# Main.net
KiCad netlist of a schematic drawn in Altium Designer
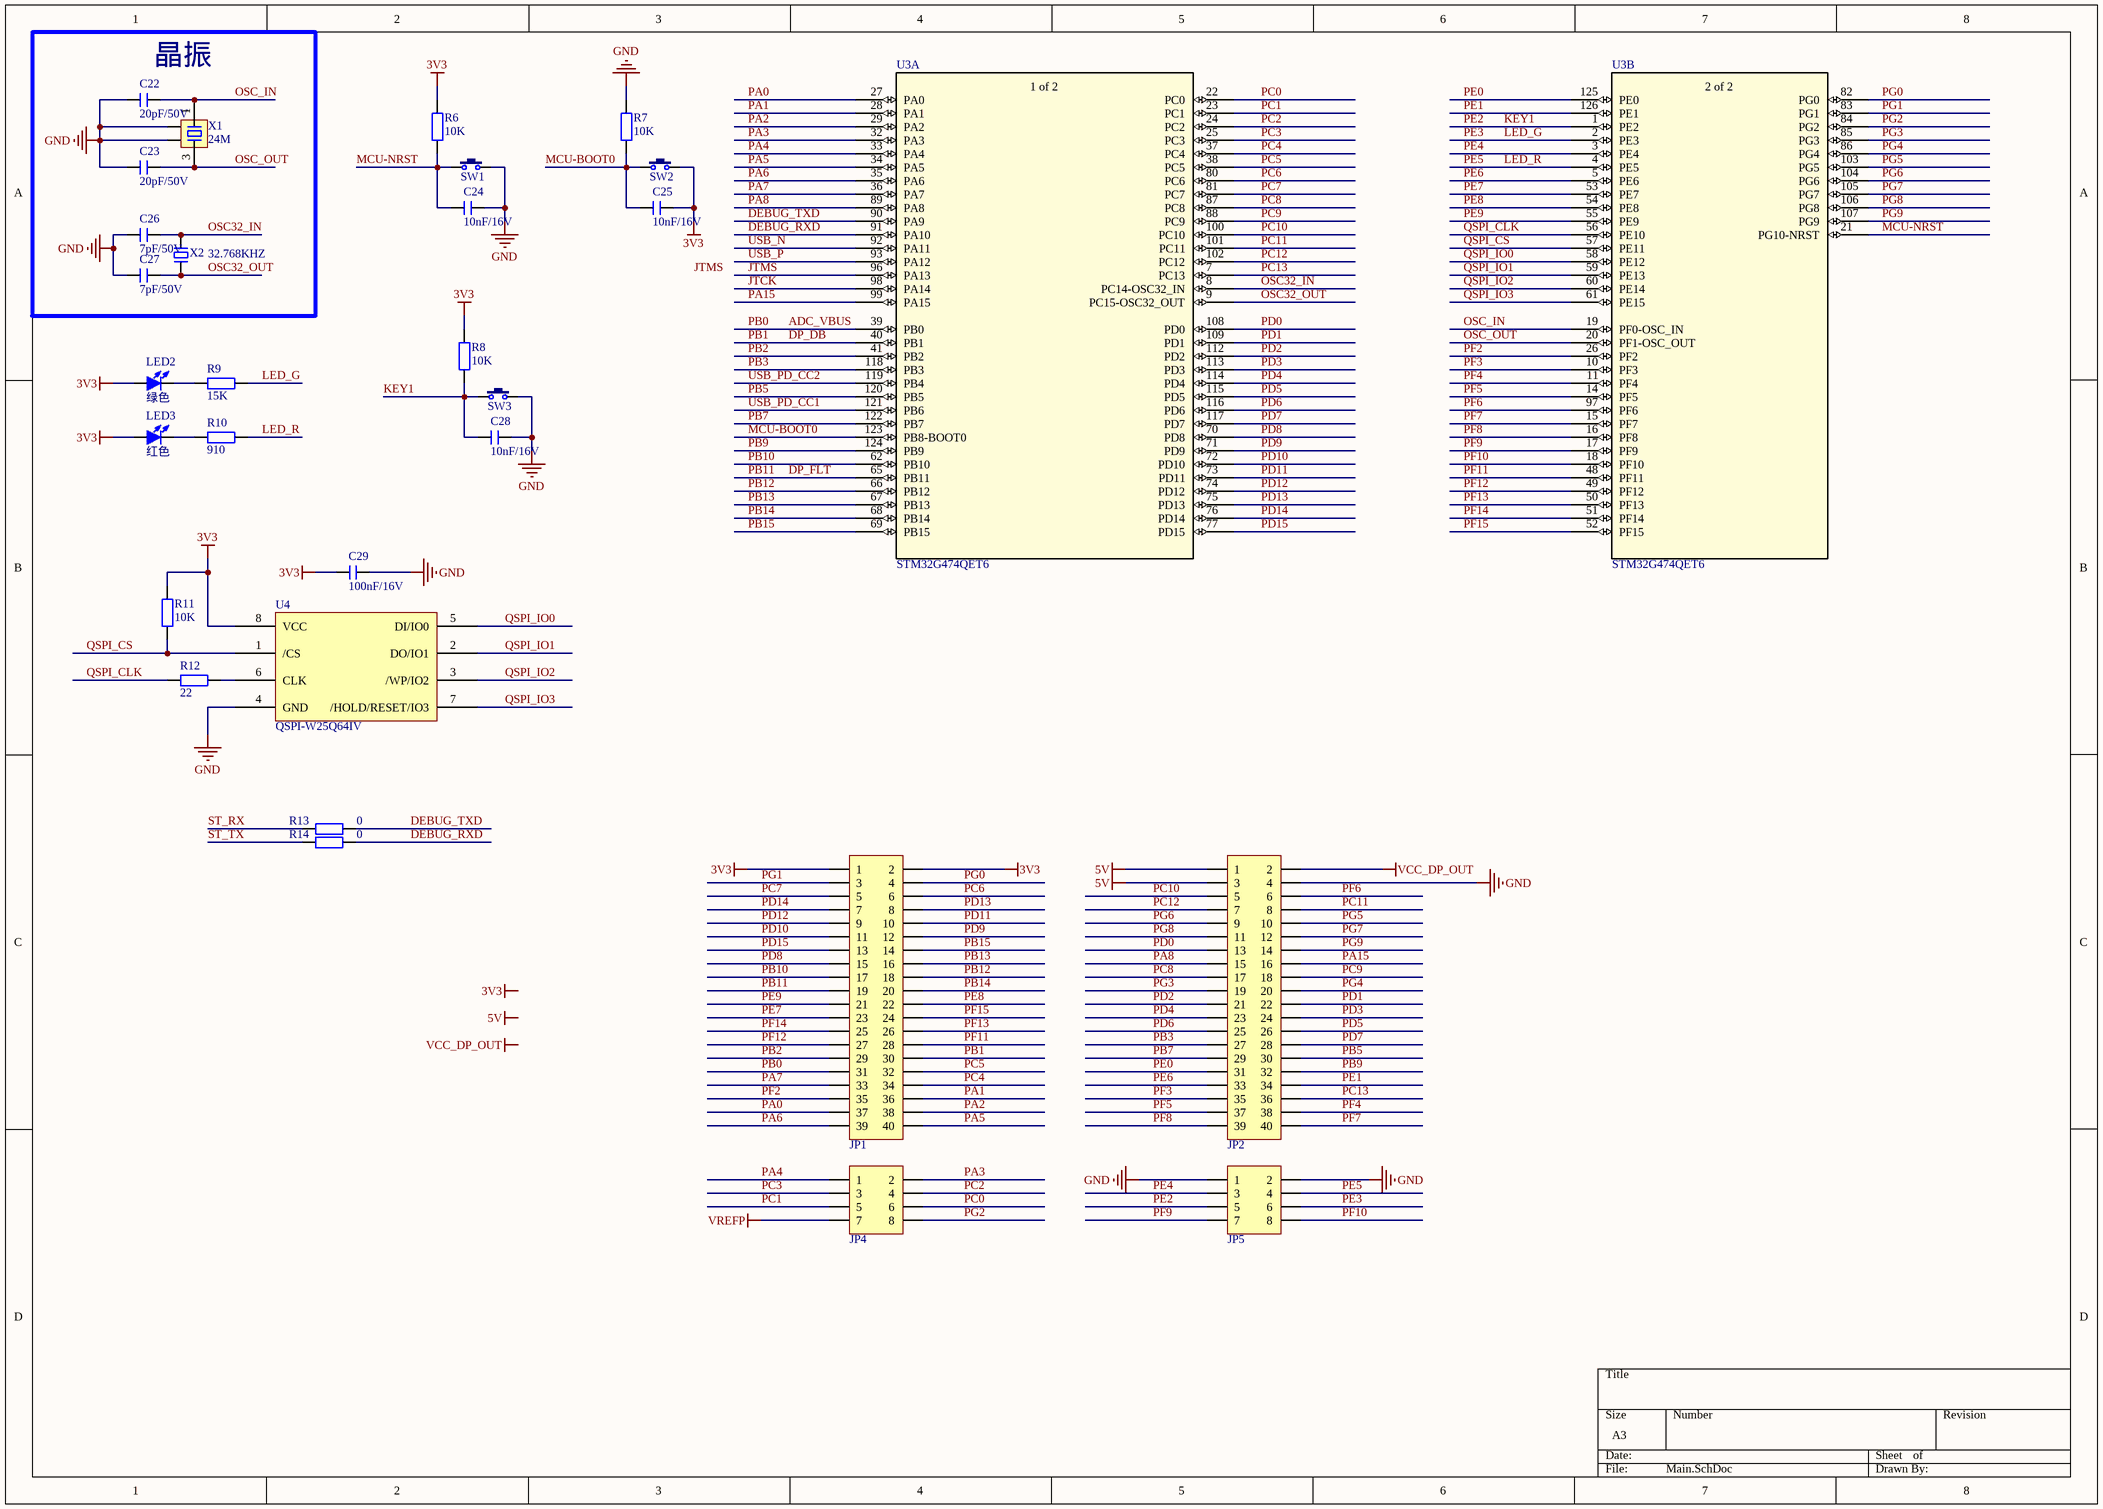
[diagram p0: Main.SchDoc]

(export (version "E")
  (design (tool "Eeschema 10.0.6"))
  (components
    (comp (ref "C22")
      (value "20pF/50V")
      (footprint "C 0402_L")
      (description "贴片电容")
      (libsource (lib "3.1   - 电阻-电容-电感") (part "C"))
    )
    (comp (ref "C23")
      (value "20pF/50V")
      (footprint "C 0402_L")
      (description "贴片电容")
      (libsource (lib "3.1   - 电阻-电容-电感") (part "C"))
    )
    (comp (ref "C24")
      (value "10nF/16V")
      (footprint "C 0402_L")
      (description "贴片电容")
      (libsource (lib "3.1   - 电阻-电容-电感") (part "C"))
    )
    (comp (ref "C25")
      (value "10nF/16V")
      (footprint "C 0402_L")
      (description "贴片电容")
      (libsource (lib "3.1   - 电阻-电容-电感") (part "C"))
    )
    (comp (ref "C26")
      (value "7pF/50V")
      (footprint "C 0402_L")
      (description "贴片电容")
      (libsource (lib "3.1   - 电阻-电容-电感") (part "C"))
    )
    (comp (ref "C27")
      (value "7pF/50V")
      (footprint "C 0402_L")
      (description "贴片电容")
      (libsource (lib "3.1   - 电阻-电容-电感") (part "C"))
    )
    (comp (ref "C28")
      (value "10nF/16V")
      (footprint "C 0402_L")
      (description "贴片电容")
      (libsource (lib "3.1   - 电阻-电容-电感") (part "C"))
    )
    (comp (ref "C29")
      (value "100nF/16V")
      (footprint "C 0402_L")
      (description "贴片电容")
      (libsource (lib "3.1   - 电阻-电容-电感") (part "C"))
    )
    (comp (ref "JP1")
      (value "Header 2X11")
      (footprint "HDR2.54-LI-2x20P")
      (description "20*2P接插件")
      (fields (field (name "版权归属") "源创客"))
      (libsource (lib "4.5   - 接插件-脚距2.54") (part "Header 20X2"))
    )
    (comp (ref "JP2")
      (value "Header 2X11")
      (footprint "HDR2.54-LI-2x20P")
      (description "20*2P接插件")
      (fields (field (name "版权归属") "源创客"))
      (libsource (lib "4.5   - 接插件-脚距2.54") (part "Header 20X2"))
    )
    (comp (ref "JP4")
      (value "Header 4X2")
      (footprint "HDR2.54-LI-2x4P")
      (description "4*2P接插件")
      (fields (field (name "版权归属") "源创客"))
      (libsource (lib "4.5   - 接插件-脚距2.54") (part "Header 4X2"))
    )
    (comp (ref "JP5")
      (value "Header 4X2")
      (footprint "HDR2.54-LI-2x4P")
      (description "4*2P接插件")
      (fields (field (name "版权归属") "源创客"))
      (libsource (lib "4.5   - 接插件-脚距2.54") (part "Header 4X2"))
    )
    (comp (ref "LED2")
      (value "绿色")
      (footprint "LED")
      (description "C84267")
      (libsource (lib "9.1   - LED") (part "LED-SMD"))
    )
    (comp (ref "LED3")
      (value "红色")
      (footprint "LED")
      (description "C84267")
      (libsource (lib "9.1   - LED") (part "LED-SMD"))
    )
    (comp (ref "R6")
      (value "10K")
      (footprint "R 0402_L")
      (description "贴片电阻")
      (libsource (lib "3.1   - 电阻-电容-电感") (part "R"))
    )
    (comp (ref "R7")
      (value "10K")
      (footprint "R 0402_L")
      (description "贴片电阻")
      (libsource (lib "3.1   - 电阻-电容-电感") (part "R"))
    )
    (comp (ref "R8")
      (value "10K")
      (footprint "R 0402_L")
      (description "贴片电阻")
      (libsource (lib "3.1   - 电阻-电容-电感") (part "R"))
    )
    (comp (ref "R9")
      (value "15K")
      (footprint "R 0402_L")
      (description "贴片电阻 0402 5%")
      (libsource (lib "3.1   - 电阻-电容-电感") (part "R"))
    )
    (comp (ref "R10")
      (value "910")
      (footprint "R 0402_L")
      (description "贴片电阻 0402 5%")
      (libsource (lib "3.1   - 电阻-电容-电感") (part "R"))
    )
    (comp (ref "R11")
      (value "10K")
      (footprint "R 0402_L")
      (description "贴片电阻 0402 1%")
      (libsource (lib "3.1   - 电阻-电容-电感") (part "R"))
    )
    (comp (ref "R12")
      (value "22")
      (footprint "R 0402_L")
      (description "贴片电阻 0402 1%")
      (libsource (lib "3.1   - 电阻-电容-电感") (part "R"))
    )
    (comp (ref "R13")
      (value "0")
      (footprint "R 0402_L")
      (description "贴片电阻")
      (libsource (lib "3.1   - 电阻-电容-电感") (part "R"))
    )
    (comp (ref "R14")
      (value "0")
      (footprint "R 0402_L")
      (description "贴片电阻")
      (libsource (lib "3.1   - 电阻-电容-电感") (part "R"))
    )
    (comp (ref "SW1")
      (value "3x6x5")
      (footprint "按钮")
      (description "3x6轻触开关")
      (libsource (lib "5.1   - 按键-开关") (part "TSW 3x6"))
    )
    (comp (ref "SW2")
      (value "3x6x5")
      (footprint "按钮")
      (description "3x6轻触开关")
      (libsource (lib "5.1   - 按键-开关") (part "TSW 3x6"))
    )
    (comp (ref "SW3")
      (value "3x6x5")
      (footprint "按钮")
      (description "3x6轻触开关")
      (libsource (lib "5.1   - 按键-开关") (part "TSW 3x6"))
    )
    (comp (ref "U3")
      (value "STM32G474QET6")
      (footprint "LQFP128 14x14_L")
      (description "No Description Available")
      (fields (field (name "COPYRIGHT") "Copyright (C) 2018 Accelerated Designs. All rights reserved"))
      (libsource (lib "2021-04-22_13-53-57") (part "STM32G474QET6"))
    )
    (comp (ref "U4")
      (value "QSPI-W25Q64IV")
      (footprint "QSPI")
      (libsource (lib "AltiumV15") (part "QSPI-W25Q256IV"))
    )
    (comp (ref "X1")
      (value "24M")
      (footprint "OSC 3225-4P")
      (description "4脚无源晶振")
      (libsource (lib "10.1 - 保险丝-晶振") (part "XTAL-4P"))
    )
    (comp (ref "X2")
      (value "32.768KHZ")
      (footprint "OSC 3215-2P")
      (description "2脚无源脚晶振")
      (libsource (lib "10.1 - 保险丝-晶振") (part "XTAL-2P"))
    )
  )
  (nets
    (net (code "1") (name "/ADC_VBUS") (class "Default")
      (node (ref "JP1") (pin "31") (pinfunction "31_31") (pintype "passive"))
      (node (ref "U3") (pin "39") (pinfunction "PB0_39") (pintype "bidirectional"))
    )
    (net (code "2") (name "/DEBUG_RXD") (class "Default")
      (node (ref "R14") (pin "2") (pinfunction "2_2") (pintype "passive"))
      (node (ref "U3") (pin "91") (pinfunction "PA10_91") (pintype "bidirectional"))
    )
    (net (code "3") (name "/DEBUG_TXD") (class "Default")
      (node (ref "R13") (pin "2") (pinfunction "2_2") (pintype "passive"))
      (node (ref "U3") (pin "90") (pinfunction "PA9_90") (pintype "bidirectional"))
    )
    (net (code "4") (name "/DP_DB") (class "Default")
      (node (ref "JP1") (pin "30") (pinfunction "30_30") (pintype "passive"))
      (node (ref "U3") (pin "40") (pinfunction "PB1_40") (pintype "bidirectional"))
    )
    (net (code "5") (name "/DP_FLT") (class "Default")
      (node (ref "JP1") (pin "19") (pinfunction "19_19") (pintype "passive"))
      (node (ref "U3") (pin "65") (pinfunction "PB11_65") (pintype "bidirectional"))
    )
    (net (code "6") (name "/JTCK") (class "Default")
      (node (ref "U3") (pin "98") (pinfunction "PA14_98") (pintype "bidirectional"))
    )
    (net (code "7") (name "/JTMS") (class "Default")
      (node (ref "U3") (pin "96") (pinfunction "PA13_96") (pintype "bidirectional"))
    )
    (net (code "8") (name "/KEY1") (class "Default")
      (node (ref "C28") (pin "1") (pinfunction "1_1") (pintype "passive"))
      (node (ref "JP5") (pin "5") (pinfunction "5_5") (pintype "passive"))
      (node (ref "R8") (pin "1") (pinfunction "1_1") (pintype "passive"))
      (node (ref "SW3") (pin "1") (pinfunction "1_1") (pintype "passive"))
      (node (ref "U3") (pin "1") (pinfunction "PE2_1") (pintype "bidirectional"))
    )
    (net (code "9") (name "/LED_G") (class "Default")
      (node (ref "JP5") (pin "6") (pinfunction "6_6") (pintype "passive"))
      (node (ref "R9") (pin "1") (pinfunction "1_1") (pintype "passive"))
      (node (ref "U3") (pin "2") (pinfunction "PE3_2") (pintype "bidirectional"))
    )
    (net (code "10") (name "/LED_R") (class "Default")
      (node (ref "JP5") (pin "4") (pinfunction "4_4") (pintype "passive"))
      (node (ref "R10") (pin "1") (pinfunction "1_1") (pintype "passive"))
      (node (ref "U3") (pin "4") (pinfunction "PE5_4") (pintype "bidirectional"))
    )
    (net (code "11") (name "/MCU-BOOT0") (class "Default")
      (node (ref "C25") (pin "1") (pinfunction "1_1") (pintype "passive"))
      (node (ref "R7") (pin "1") (pinfunction "1_1") (pintype "passive"))
      (node (ref "SW2") (pin "1") (pinfunction "1_1") (pintype "passive"))
      (node (ref "U3") (pin "123") (pinfunction "PB8-BOOT0_123") (pintype "bidirectional"))
    )
    (net (code "12") (name "/MCU-NRST") (class "Default")
      (node (ref "C24") (pin "1") (pinfunction "1_1") (pintype "passive"))
      (node (ref "R6") (pin "1") (pinfunction "1_1") (pintype "passive"))
      (node (ref "SW1") (pin "1") (pinfunction "1_1") (pintype "passive"))
      (node (ref "U3") (pin "21") (pinfunction "PG10-NRST_21") (pintype "bidirectional"))
    )
    (net (code "13") (name "/OSC32_IN") (class "Default")
      (node (ref "C26") (pin "2") (pinfunction "2_2") (pintype "passive"))
      (node (ref "U3") (pin "8") (pinfunction "PC14-OSC32_IN_8") (pintype "bidirectional"))
      (node (ref "X2") (pin "2") (pinfunction "2_2") (pintype "passive"))
    )
    (net (code "14") (name "/OSC32_OUT") (class "Default")
      (node (ref "C27") (pin "2") (pinfunction "2_2") (pintype "passive"))
      (node (ref "U3") (pin "9") (pinfunction "PC15-OSC32_OUT_9") (pintype "bidirectional"))
      (node (ref "X2") (pin "1") (pinfunction "1_1") (pintype "passive"))
    )
    (net (code "15") (name "/OSC_IN") (class "Default")
      (node (ref "C22") (pin "2") (pinfunction "2_2") (pintype "passive"))
      (node (ref "U3") (pin "19") (pinfunction "PF0-OSC_IN_19") (pintype "bidirectional"))
      (node (ref "X1") (pin "1") (pinfunction "1_1") (pintype "passive"))
    )
    (net (code "16") (name "/OSC_OUT") (class "Default")
      (node (ref "C23") (pin "2") (pinfunction "2_2") (pintype "passive"))
      (node (ref "U3") (pin "20") (pinfunction "PF1-OSC_OUT_20") (pintype "bidirectional"))
      (node (ref "X1") (pin "3") (pinfunction "3_3") (pintype "passive"))
    )
    (net (code "17") (name "/PA0") (class "Default")
      (node (ref "JP1") (pin "37") (pinfunction "37_37") (pintype "passive"))
      (node (ref "U3") (pin "27") (pinfunction "PA0_27") (pintype "bidirectional"))
    )
    (net (code "18") (name "/PA1") (class "Default")
      (node (ref "JP1") (pin "36") (pinfunction "36_36") (pintype "passive"))
      (node (ref "U3") (pin "28") (pinfunction "PA1_28") (pintype "bidirectional"))
    )
    (net (code "19") (name "/PA2") (class "Default")
      (node (ref "JP1") (pin "38") (pinfunction "38_38") (pintype "passive"))
      (node (ref "U3") (pin "29") (pinfunction "PA2_29") (pintype "bidirectional"))
    )
    (net (code "20") (name "/PA3") (class "Default")
      (node (ref "JP4") (pin "2") (pinfunction "2_2") (pintype "passive"))
      (node (ref "U3") (pin "32") (pinfunction "PA3_32") (pintype "bidirectional"))
    )
    (net (code "21") (name "/PA4") (class "Default")
      (node (ref "JP4") (pin "1") (pinfunction "1_1") (pintype "passive"))
      (node (ref "U3") (pin "33") (pinfunction "PA4_33") (pintype "bidirectional"))
    )
    (net (code "22") (name "/PA5") (class "Default")
      (node (ref "JP1") (pin "40") (pinfunction "40_40") (pintype "passive"))
      (node (ref "U3") (pin "34") (pinfunction "PA5_34") (pintype "bidirectional"))
    )
    (net (code "23") (name "/PA6") (class "Default")
      (node (ref "JP1") (pin "39") (pinfunction "39_39") (pintype "passive"))
      (node (ref "U3") (pin "35") (pinfunction "PA6_35") (pintype "bidirectional"))
    )
    (net (code "24") (name "/PA7") (class "Default")
      (node (ref "JP1") (pin "33") (pinfunction "33_33") (pintype "passive"))
      (node (ref "U3") (pin "36") (pinfunction "PA7_36") (pintype "bidirectional"))
    )
    (net (code "25") (name "/PA8") (class "Default")
      (node (ref "JP2") (pin "15") (pinfunction "15_15") (pintype "passive"))
      (node (ref "U3") (pin "89") (pinfunction "PA8_89") (pintype "bidirectional"))
    )
    (net (code "26") (name "/PA15") (class "Default")
      (node (ref "JP2") (pin "16") (pinfunction "16_16") (pintype "passive"))
      (node (ref "U3") (pin "99") (pinfunction "PA15_99") (pintype "bidirectional"))
    )
    (net (code "27") (name "/PB2") (class "Default")
      (node (ref "JP1") (pin "29") (pinfunction "29_29") (pintype "passive"))
      (node (ref "U3") (pin "41") (pinfunction "PB2_41") (pintype "bidirectional"))
    )
    (net (code "28") (name "/PB3") (class "Default")
      (node (ref "JP2") (pin "27") (pinfunction "27_27") (pintype "passive"))
      (node (ref "U3") (pin "118") (pinfunction "PB3_118") (pintype "bidirectional"))
    )
    (net (code "29") (name "/PB5") (class "Default")
      (node (ref "JP2") (pin "30") (pinfunction "30_30") (pintype "passive"))
      (node (ref "U3") (pin "120") (pinfunction "PB5_120") (pintype "bidirectional"))
    )
    (net (code "30") (name "/PB7") (class "Default")
      (node (ref "JP2") (pin "29") (pinfunction "29_29") (pintype "passive"))
      (node (ref "U3") (pin "122") (pinfunction "PB7_122") (pintype "bidirectional"))
    )
    (net (code "31") (name "/PB9") (class "Default")
      (node (ref "JP2") (pin "32") (pinfunction "32_32") (pintype "passive"))
      (node (ref "U3") (pin "124") (pinfunction "PB9_124") (pintype "bidirectional"))
    )
    (net (code "32") (name "/PB10") (class "Default")
      (node (ref "JP1") (pin "17") (pinfunction "17_17") (pintype "passive"))
      (node (ref "U3") (pin "62") (pinfunction "PB10_62") (pintype "bidirectional"))
    )
    (net (code "33") (name "/PB12") (class "Default")
      (node (ref "JP1") (pin "18") (pinfunction "18_18") (pintype "passive"))
      (node (ref "U3") (pin "66") (pinfunction "PB12_66") (pintype "bidirectional"))
    )
    (net (code "34") (name "/PB13") (class "Default")
      (node (ref "JP1") (pin "16") (pinfunction "16_16") (pintype "passive"))
      (node (ref "U3") (pin "67") (pinfunction "PB13_67") (pintype "bidirectional"))
    )
    (net (code "35") (name "/PB14") (class "Default")
      (node (ref "JP1") (pin "20") (pinfunction "20_20") (pintype "passive"))
      (node (ref "U3") (pin "68") (pinfunction "PB14_68") (pintype "bidirectional"))
    )
    (net (code "36") (name "/PB15") (class "Default")
      (node (ref "JP1") (pin "14") (pinfunction "14_14") (pintype "passive"))
      (node (ref "U3") (pin "69") (pinfunction "PB15_69") (pintype "bidirectional"))
    )
    (net (code "37") (name "/PC0") (class "Default")
      (node (ref "JP4") (pin "6") (pinfunction "6_6") (pintype "passive"))
      (node (ref "U3") (pin "22") (pinfunction "PC0_22") (pintype "bidirectional"))
    )
    (net (code "38") (name "/PC1") (class "Default")
      (node (ref "JP4") (pin "5") (pinfunction "5_5") (pintype "passive"))
      (node (ref "U3") (pin "23") (pinfunction "PC1_23") (pintype "bidirectional"))
    )
    (net (code "39") (name "/PC2") (class "Default")
      (node (ref "JP4") (pin "4") (pinfunction "4_4") (pintype "passive"))
      (node (ref "U3") (pin "24") (pinfunction "PC2_24") (pintype "bidirectional"))
    )
    (net (code "40") (name "/PC3") (class "Default")
      (node (ref "JP4") (pin "3") (pinfunction "3_3") (pintype "passive"))
      (node (ref "U3") (pin "25") (pinfunction "PC3_25") (pintype "bidirectional"))
    )
    (net (code "41") (name "/PC4") (class "Default")
      (node (ref "JP1") (pin "34") (pinfunction "34_34") (pintype "passive"))
      (node (ref "U3") (pin "37") (pinfunction "PC4_37") (pintype "bidirectional"))
    )
    (net (code "42") (name "/PC5") (class "Default")
      (node (ref "JP1") (pin "32") (pinfunction "32_32") (pintype "passive"))
      (node (ref "U3") (pin "38") (pinfunction "PC5_38") (pintype "bidirectional"))
    )
    (net (code "43") (name "/PC6") (class "Default")
      (node (ref "JP1") (pin "6") (pinfunction "6_6") (pintype "passive"))
      (node (ref "U3") (pin "80") (pinfunction "PC6_80") (pintype "bidirectional"))
    )
    (net (code "44") (name "/PC7") (class "Default")
      (node (ref "JP1") (pin "5") (pinfunction "5_5") (pintype "passive"))
      (node (ref "U3") (pin "81") (pinfunction "PC7_81") (pintype "bidirectional"))
    )
    (net (code "45") (name "/PC8") (class "Default")
      (node (ref "JP2") (pin "17") (pinfunction "17_17") (pintype "passive"))
      (node (ref "U3") (pin "87") (pinfunction "PC8_87") (pintype "bidirectional"))
    )
    (net (code "46") (name "/PC9") (class "Default")
      (node (ref "JP2") (pin "18") (pinfunction "18_18") (pintype "passive"))
      (node (ref "U3") (pin "88") (pinfunction "PC9_88") (pintype "bidirectional"))
    )
    (net (code "47") (name "/PC10") (class "Default")
      (node (ref "JP2") (pin "5") (pinfunction "5_5") (pintype "passive"))
      (node (ref "U3") (pin "100") (pinfunction "PC10_100") (pintype "bidirectional"))
    )
    (net (code "48") (name "/PC11") (class "Default")
      (node (ref "JP2") (pin "8") (pinfunction "8_8") (pintype "passive"))
      (node (ref "U3") (pin "101") (pinfunction "PC11_101") (pintype "bidirectional"))
    )
    (net (code "49") (name "/PC12") (class "Default")
      (node (ref "JP2") (pin "7") (pinfunction "7_7") (pintype "passive"))
      (node (ref "U3") (pin "102") (pinfunction "PC12_102") (pintype "bidirectional"))
    )
    (net (code "50") (name "/PC13") (class "Default")
      (node (ref "JP2") (pin "36") (pinfunction "36_36") (pintype "passive"))
      (node (ref "U3") (pin "7") (pinfunction "PC13_7") (pintype "bidirectional"))
    )
    (net (code "51") (name "/PD0") (class "Default")
      (node (ref "JP2") (pin "13") (pinfunction "13_13") (pintype "passive"))
      (node (ref "U3") (pin "108") (pinfunction "PD0_108") (pintype "bidirectional"))
    )
    (net (code "52") (name "/PD1") (class "Default")
      (node (ref "JP2") (pin "22") (pinfunction "22_22") (pintype "passive"))
      (node (ref "U3") (pin "109") (pinfunction "PD1_109") (pintype "bidirectional"))
    )
    (net (code "53") (name "/PD2") (class "Default")
      (node (ref "JP2") (pin "21") (pinfunction "21_21") (pintype "passive"))
      (node (ref "U3") (pin "112") (pinfunction "PD2_112") (pintype "bidirectional"))
    )
    (net (code "54") (name "/PD3") (class "Default")
      (node (ref "JP2") (pin "24") (pinfunction "24_24") (pintype "passive"))
      (node (ref "U3") (pin "113") (pinfunction "PD3_113") (pintype "bidirectional"))
    )
    (net (code "55") (name "/PD4") (class "Default")
      (node (ref "JP2") (pin "23") (pinfunction "23_23") (pintype "passive"))
      (node (ref "U3") (pin "114") (pinfunction "PD4_114") (pintype "bidirectional"))
    )
    (net (code "56") (name "/PD5") (class "Default")
      (node (ref "JP2") (pin "26") (pinfunction "26_26") (pintype "passive"))
      (node (ref "U3") (pin "115") (pinfunction "PD5_115") (pintype "bidirectional"))
    )
    (net (code "57") (name "/PD6") (class "Default")
      (node (ref "JP2") (pin "25") (pinfunction "25_25") (pintype "passive"))
      (node (ref "U3") (pin "116") (pinfunction "PD6_116") (pintype "bidirectional"))
    )
    (net (code "58") (name "/PD7") (class "Default")
      (node (ref "JP2") (pin "28") (pinfunction "28_28") (pintype "passive"))
      (node (ref "U3") (pin "117") (pinfunction "PD7_117") (pintype "bidirectional"))
    )
    (net (code "59") (name "/PD8") (class "Default")
      (node (ref "JP1") (pin "15") (pinfunction "15_15") (pintype "passive"))
      (node (ref "U3") (pin "70") (pinfunction "PD8_70") (pintype "bidirectional"))
    )
    (net (code "60") (name "/PD9") (class "Default")
      (node (ref "JP1") (pin "12") (pinfunction "12_12") (pintype "passive"))
      (node (ref "U3") (pin "71") (pinfunction "PD9_71") (pintype "bidirectional"))
    )
    (net (code "61") (name "/PD10") (class "Default")
      (node (ref "JP1") (pin "11") (pinfunction "11_11") (pintype "passive"))
      (node (ref "U3") (pin "72") (pinfunction "PD10_72") (pintype "bidirectional"))
    )
    (net (code "62") (name "/PD11") (class "Default")
      (node (ref "JP1") (pin "10") (pinfunction "10_10") (pintype "passive"))
      (node (ref "U3") (pin "73") (pinfunction "PD11_73") (pintype "bidirectional"))
    )
    (net (code "63") (name "/PD12") (class "Default")
      (node (ref "JP1") (pin "9") (pinfunction "9_9") (pintype "passive"))
      (node (ref "U3") (pin "74") (pinfunction "PD12_74") (pintype "bidirectional"))
    )
    (net (code "64") (name "/PD13") (class "Default")
      (node (ref "JP1") (pin "8") (pinfunction "8_8") (pintype "passive"))
      (node (ref "U3") (pin "75") (pinfunction "PD13_75") (pintype "bidirectional"))
    )
    (net (code "65") (name "/PD14") (class "Default")
      (node (ref "JP1") (pin "7") (pinfunction "7_7") (pintype "passive"))
      (node (ref "U3") (pin "76") (pinfunction "PD14_76") (pintype "bidirectional"))
    )
    (net (code "66") (name "/PD15") (class "Default")
      (node (ref "JP1") (pin "13") (pinfunction "13_13") (pintype "passive"))
      (node (ref "U3") (pin "77") (pinfunction "PD15_77") (pintype "bidirectional"))
    )
    (net (code "67") (name "/PE0") (class "Default")
      (node (ref "JP2") (pin "31") (pinfunction "31_31") (pintype "passive"))
      (node (ref "U3") (pin "125") (pinfunction "PE0_125") (pintype "bidirectional"))
    )
    (net (code "68") (name "/PE1") (class "Default")
      (node (ref "JP2") (pin "34") (pinfunction "34_34") (pintype "passive"))
      (node (ref "U3") (pin "126") (pinfunction "PE1_126") (pintype "bidirectional"))
    )
    (net (code "69") (name "/PE4") (class "Default")
      (node (ref "JP5") (pin "3") (pinfunction "3_3") (pintype "passive"))
      (node (ref "U3") (pin "3") (pinfunction "PE4_3") (pintype "bidirectional"))
    )
    (net (code "70") (name "/PE6") (class "Default")
      (node (ref "JP2") (pin "33") (pinfunction "33_33") (pintype "passive"))
      (node (ref "U3") (pin "5") (pinfunction "PE6_5") (pintype "bidirectional"))
    )
    (net (code "71") (name "/PE7") (class "Default")
      (node (ref "JP1") (pin "23") (pinfunction "23_23") (pintype "passive"))
      (node (ref "U3") (pin "53") (pinfunction "PE7_53") (pintype "bidirectional"))
    )
    (net (code "72") (name "/PE8") (class "Default")
      (node (ref "JP1") (pin "22") (pinfunction "22_22") (pintype "passive"))
      (node (ref "U3") (pin "54") (pinfunction "PE8_54") (pintype "bidirectional"))
    )
    (net (code "73") (name "/PE9") (class "Default")
      (node (ref "JP1") (pin "21") (pinfunction "21_21") (pintype "passive"))
      (node (ref "U3") (pin "55") (pinfunction "PE9_55") (pintype "bidirectional"))
    )
    (net (code "74") (name "/PF2") (class "Default")
      (node (ref "JP1") (pin "35") (pinfunction "35_35") (pintype "passive"))
      (node (ref "U3") (pin "26") (pinfunction "PF2_26") (pintype "bidirectional"))
    )
    (net (code "75") (name "/PF3") (class "Default")
      (node (ref "JP2") (pin "35") (pinfunction "35_35") (pintype "passive"))
      (node (ref "U3") (pin "10") (pinfunction "PF3_10") (pintype "bidirectional"))
    )
    (net (code "76") (name "/PF4") (class "Default")
      (node (ref "JP2") (pin "38") (pinfunction "38_38") (pintype "passive"))
      (node (ref "U3") (pin "11") (pinfunction "PF4_11") (pintype "bidirectional"))
    )
    (net (code "77") (name "/PF5") (class "Default")
      (node (ref "JP2") (pin "37") (pinfunction "37_37") (pintype "passive"))
      (node (ref "U3") (pin "14") (pinfunction "PF5_14") (pintype "bidirectional"))
    )
    (net (code "78") (name "/PF6") (class "Default")
      (node (ref "JP2") (pin "6") (pinfunction "6_6") (pintype "passive"))
      (node (ref "U3") (pin "97") (pinfunction "PF6_97") (pintype "bidirectional"))
    )
    (net (code "79") (name "/PF7") (class "Default")
      (node (ref "JP2") (pin "40") (pinfunction "40_40") (pintype "passive"))
      (node (ref "U3") (pin "15") (pinfunction "PF7_15") (pintype "bidirectional"))
    )
    (net (code "80") (name "/PF8") (class "Default")
      (node (ref "JP2") (pin "39") (pinfunction "39_39") (pintype "passive"))
      (node (ref "U3") (pin "16") (pinfunction "PF8_16") (pintype "bidirectional"))
    )
    (net (code "81") (name "/PF9") (class "Default")
      (node (ref "JP5") (pin "7") (pinfunction "7_7") (pintype "passive"))
      (node (ref "U3") (pin "17") (pinfunction "PF9_17") (pintype "bidirectional"))
    )
    (net (code "82") (name "/PF10") (class "Default")
      (node (ref "JP5") (pin "8") (pinfunction "8_8") (pintype "passive"))
      (node (ref "U3") (pin "18") (pinfunction "PF10_18") (pintype "bidirectional"))
    )
    (net (code "83") (name "/PF11") (class "Default")
      (node (ref "JP1") (pin "28") (pinfunction "28_28") (pintype "passive"))
      (node (ref "U3") (pin "48") (pinfunction "PF11_48") (pintype "bidirectional"))
    )
    (net (code "84") (name "/PF12") (class "Default")
      (node (ref "JP1") (pin "27") (pinfunction "27_27") (pintype "passive"))
      (node (ref "U3") (pin "49") (pinfunction "PF12_49") (pintype "bidirectional"))
    )
    (net (code "85") (name "/PF13") (class "Default")
      (node (ref "JP1") (pin "26") (pinfunction "26_26") (pintype "passive"))
      (node (ref "U3") (pin "50") (pinfunction "PF13_50") (pintype "bidirectional"))
    )
    (net (code "86") (name "/PF14") (class "Default")
      (node (ref "JP1") (pin "25") (pinfunction "25_25") (pintype "passive"))
      (node (ref "U3") (pin "51") (pinfunction "PF14_51") (pintype "bidirectional"))
    )
    (net (code "87") (name "/PF15") (class "Default")
      (node (ref "JP1") (pin "24") (pinfunction "24_24") (pintype "passive"))
      (node (ref "U3") (pin "52") (pinfunction "PF15_52") (pintype "bidirectional"))
    )
    (net (code "88") (name "/PG0") (class "Default")
      (node (ref "JP1") (pin "4") (pinfunction "4_4") (pintype "passive"))
      (node (ref "U3") (pin "82") (pinfunction "PG0_82") (pintype "bidirectional"))
    )
    (net (code "89") (name "/PG1") (class "Default")
      (node (ref "JP1") (pin "3") (pinfunction "3_3") (pintype "passive"))
      (node (ref "U3") (pin "83") (pinfunction "PG1_83") (pintype "bidirectional"))
    )
    (net (code "90") (name "/PG2") (class "Default")
      (node (ref "JP4") (pin "8") (pinfunction "8_8") (pintype "passive"))
      (node (ref "U3") (pin "84") (pinfunction "PG2_84") (pintype "bidirectional"))
    )
    (net (code "91") (name "/PG3") (class "Default")
      (node (ref "JP2") (pin "19") (pinfunction "19_19") (pintype "passive"))
      (node (ref "U3") (pin "85") (pinfunction "PG3_85") (pintype "bidirectional"))
    )
    (net (code "92") (name "/PG4") (class "Default")
      (node (ref "JP2") (pin "20") (pinfunction "20_20") (pintype "passive"))
      (node (ref "U3") (pin "86") (pinfunction "PG4_86") (pintype "bidirectional"))
    )
    (net (code "93") (name "/PG5") (class "Default")
      (node (ref "JP2") (pin "10") (pinfunction "10_10") (pintype "passive"))
      (node (ref "U3") (pin "103") (pinfunction "PG5_103") (pintype "bidirectional"))
    )
    (net (code "94") (name "/PG6") (class "Default")
      (node (ref "JP2") (pin "9") (pinfunction "9_9") (pintype "passive"))
      (node (ref "U3") (pin "104") (pinfunction "PG6_104") (pintype "bidirectional"))
    )
    (net (code "95") (name "/PG7") (class "Default")
      (node (ref "JP2") (pin "12") (pinfunction "12_12") (pintype "passive"))
      (node (ref "U3") (pin "105") (pinfunction "PG7_105") (pintype "bidirectional"))
    )
    (net (code "96") (name "/PG8") (class "Default")
      (node (ref "JP2") (pin "11") (pinfunction "11_11") (pintype "passive"))
      (node (ref "U3") (pin "106") (pinfunction "PG8_106") (pintype "bidirectional"))
    )
    (net (code "97") (name "/PG9") (class "Default")
      (node (ref "JP2") (pin "14") (pinfunction "14_14") (pintype "passive"))
      (node (ref "U3") (pin "107") (pinfunction "PG9_107") (pintype "bidirectional"))
    )
    (net (code "98") (name "/QSPI_CLK") (class "Default")
      (node (ref "R12") (pin "1") (pinfunction "1_1") (pintype "passive"))
      (node (ref "U3") (pin "56") (pinfunction "PE10_56") (pintype "bidirectional"))
    )
    (net (code "99") (name "/QSPI_CS") (class "Default")
      (node (ref "R11") (pin "2") (pinfunction "2_2") (pintype "passive"))
      (node (ref "U3") (pin "57") (pinfunction "PE11_57") (pintype "bidirectional"))
      (node (ref "U4") (pin "1") (pinfunction "/CS_1") (pintype "passive"))
    )
    (net (code "100") (name "/QSPI_IO0") (class "Default")
      (node (ref "U3") (pin "58") (pinfunction "PE12_58") (pintype "bidirectional"))
      (node (ref "U4") (pin "5") (pinfunction "DI/IO0_5") (pintype "passive"))
    )
    (net (code "101") (name "/QSPI_IO1") (class "Default")
      (node (ref "U3") (pin "59") (pinfunction "PE13_59") (pintype "bidirectional"))
      (node (ref "U4") (pin "2") (pinfunction "DO/IO1_2") (pintype "passive"))
    )
    (net (code "102") (name "/QSPI_IO2") (class "Default")
      (node (ref "U3") (pin "60") (pinfunction "PE14_60") (pintype "bidirectional"))
      (node (ref "U4") (pin "3") (pinfunction "/WP/IO2_3") (pintype "passive"))
    )
    (net (code "103") (name "/QSPI_IO3") (class "Default")
      (node (ref "U3") (pin "61") (pinfunction "PE15_61") (pintype "bidirectional"))
      (node (ref "U4") (pin "7") (pinfunction "/HOLD/RESET/IO3_7") (pintype "passive"))
    )
    (net (code "104") (name "/ST_RX") (class "Default")
      (node (ref "R13") (pin "1") (pinfunction "1_1") (pintype "passive"))
    )
    (net (code "105") (name "/ST_TX") (class "Default")
      (node (ref "R14") (pin "1") (pinfunction "1_1") (pintype "passive"))
    )
    (net (code "106") (name "/USB_N") (class "Default")
      (node (ref "U3") (pin "92") (pinfunction "PA11_92") (pintype "bidirectional"))
    )
    (net (code "107") (name "/USB_P") (class "Default")
      (node (ref "U3") (pin "93") (pinfunction "PA12_93") (pintype "bidirectional"))
    )
    (net (code "108") (name "/USB_PD_CC1") (class "Default")
      (node (ref "U3") (pin "121") (pinfunction "PB6_121") (pintype "bidirectional"))
    )
    (net (code "109") (name "/USB_PD_CC2") (class "Default")
      (node (ref "U3") (pin "119") (pinfunction "PB4_119") (pintype "bidirectional"))
    )
    (net (code "110") (name "3V3") (class "Default")
      (node (ref "C25") (pin "2") (pinfunction "2_2") (pintype "passive"))
      (node (ref "C29") (pin "2") (pinfunction "2_2") (pintype "passive"))
      (node (ref "JP1") (pin "1") (pinfunction "1_1") (pintype "passive"))
      (node (ref "JP1") (pin "2") (pinfunction "2_2") (pintype "passive"))
      (node (ref "LED2") (pin "1") (pinfunction "A_1") (pintype "passive"))
      (node (ref "LED3") (pin "1") (pinfunction "A_1") (pintype "passive"))
      (node (ref "R11") (pin "1") (pinfunction "1_1") (pintype "passive"))
      (node (ref "R6") (pin "2") (pinfunction "2_2") (pintype "passive"))
      (node (ref "R8") (pin "2") (pinfunction "2_2") (pintype "passive"))
      (node (ref "SW2") (pin "2") (pinfunction "2_2") (pintype "passive"))
      (node (ref "U4") (pin "8") (pinfunction "VCC_8") (pintype "passive"))
    )
    (net (code "111") (name "5V") (class "Default")
      (node (ref "JP2") (pin "1") (pinfunction "1_1") (pintype "passive"))
      (node (ref "JP2") (pin "3") (pinfunction "3_3") (pintype "passive"))
    )
    (net (code "112") (name "GND") (class "Default")
      (node (ref "C22") (pin "1") (pinfunction "1_1") (pintype "passive"))
      (node (ref "C23") (pin "1") (pinfunction "1_1") (pintype "passive"))
      (node (ref "C24") (pin "2") (pinfunction "2_2") (pintype "passive"))
      (node (ref "C26") (pin "1") (pinfunction "1_1") (pintype "passive"))
      (node (ref "C27") (pin "1") (pinfunction "1_1") (pintype "passive"))
      (node (ref "C28") (pin "2") (pinfunction "2_2") (pintype "passive"))
      (node (ref "C29") (pin "1") (pinfunction "1_1") (pintype "passive"))
      (node (ref "JP2") (pin "4") (pinfunction "4_4") (pintype "passive"))
      (node (ref "JP5") (pin "1") (pinfunction "1_1") (pintype "passive"))
      (node (ref "JP5") (pin "2") (pinfunction "2_2") (pintype "passive"))
      (node (ref "R7") (pin "2") (pinfunction "2_2") (pintype "passive"))
      (node (ref "SW1") (pin "2") (pinfunction "2_2") (pintype "passive"))
      (node (ref "SW3") (pin "2") (pinfunction "2_2") (pintype "passive"))
      (node (ref "U4") (pin "4") (pinfunction "GND_4") (pintype "passive"))
      (node (ref "X1") (pin "2") (pinfunction "2_2") (pintype "passive"))
      (node (ref "X1") (pin "4") (pinfunction "4_4") (pintype "passive"))
    )
    (net (code "113") (name "Net-(LED2-K)") (class "Default")
      (node (ref "LED2") (pin "2") (pinfunction "K_2") (pintype "passive"))
      (node (ref "R9") (pin "2") (pinfunction "2_2") (pintype "passive"))
    )
    (net (code "114") (name "Net-(LED3-K)") (class "Default")
      (node (ref "LED3") (pin "2") (pinfunction "K_2") (pintype "passive"))
      (node (ref "R10") (pin "2") (pinfunction "2_2") (pintype "passive"))
    )
    (net (code "115") (name "Net-(U4-CLK)") (class "Default")
      (node (ref "R12") (pin "2") (pinfunction "2_2") (pintype "passive"))
      (node (ref "U4") (pin "6") (pinfunction "CLK_6") (pintype "passive"))
    )
    (net (code "116") (name "VCC_DP_OUT") (class "Default")
      (node (ref "JP2") (pin "2") (pinfunction "2_2") (pintype "passive"))
    )
    (net (code "117") (name "VREFP") (class "Default")
      (node (ref "JP4") (pin "7") (pinfunction "7_7") (pintype "passive"))
    )
  )
)
